# ASA.net
KiCad netlist of a schematic drawn in Altium Designer
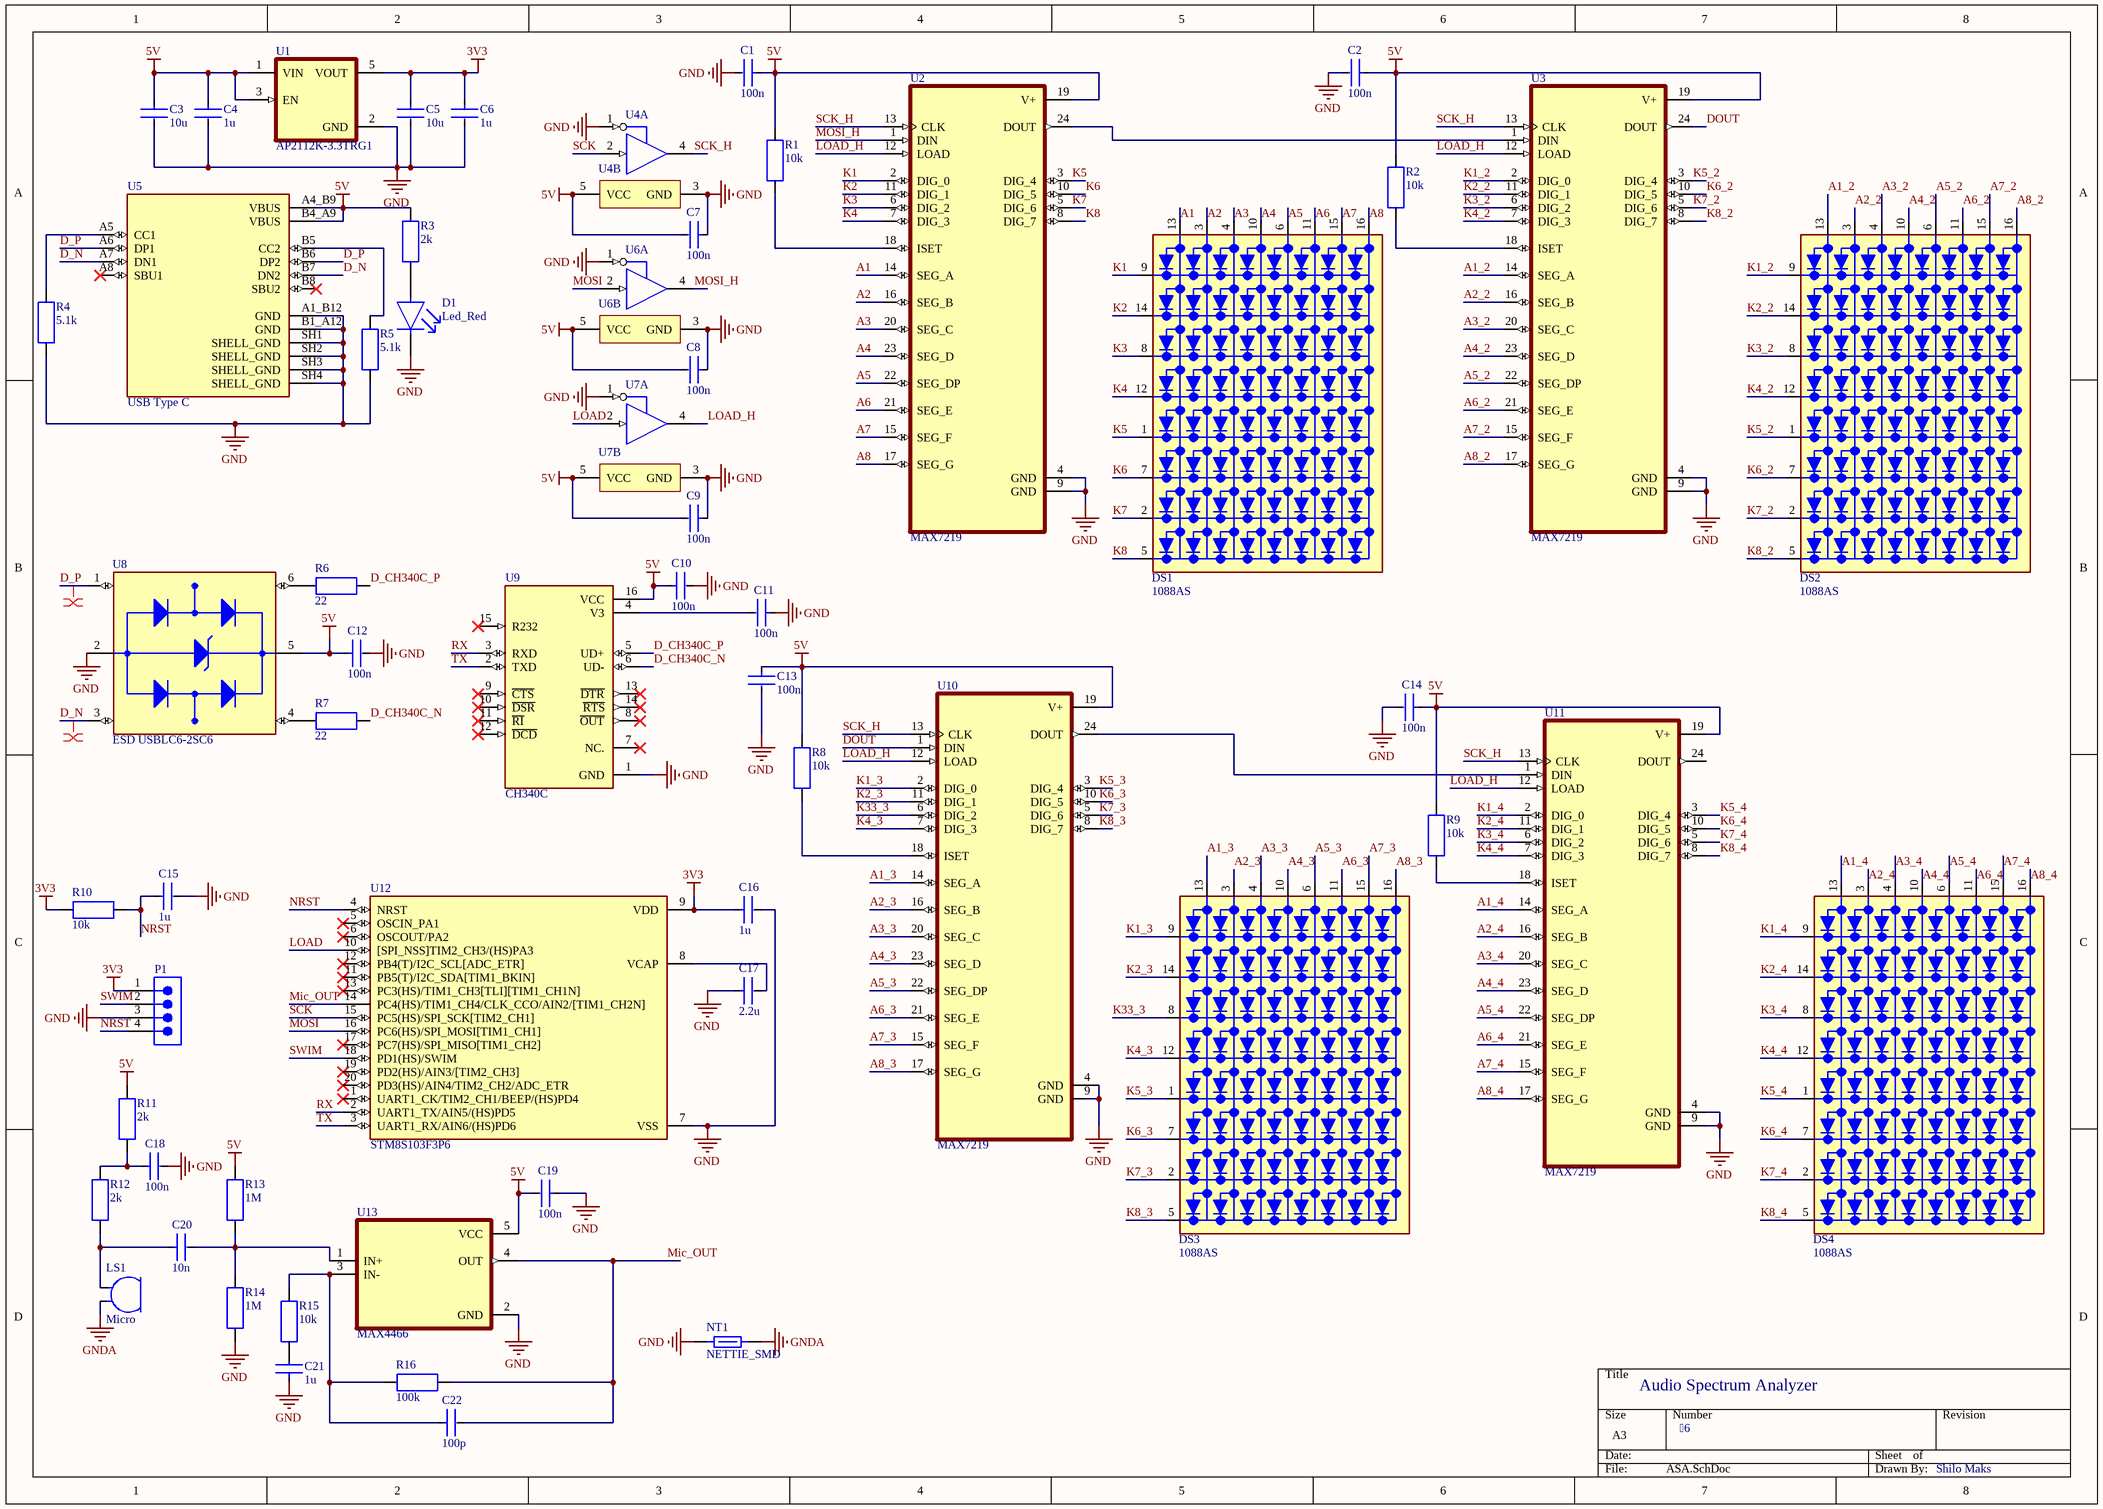
[diagram p0: ASA.SchDoc]

(export (version "E")
  (design (tool "Eeschema 10.0.6"))
  (components
    (comp (ref "C1")
      (value "100n")
      (footprint "Cap_1206")
      (fields (field (name "Comment") "Cap_1206"))
      (libsource (lib "Schlib_Spectrum_Analyzer") (part "Cap_1206"))
    )
    (comp (ref "C2")
      (value "100n")
      (footprint "Cap_1206")
      (fields (field (name "Comment") "Cap_1206"))
      (libsource (lib "Schlib_Spectrum_Analyzer") (part "Cap_1206"))
    )
    (comp (ref "C3")
      (value "10u")
      (footprint "Cap_1206")
      (fields (field (name "Comment") "Cap_1206"))
      (libsource (lib "Schlib_Spectrum_Analyzer") (part "Cap_1206"))
    )
    (comp (ref "C4")
      (value "1u")
      (footprint "Cap_1206")
      (fields (field (name "Comment") "Cap_1206"))
      (libsource (lib "Schlib_Spectrum_Analyzer") (part "Cap_1206"))
    )
    (comp (ref "C5")
      (value "10u")
      (footprint "Cap_1206")
      (fields (field (name "Comment") "Cap_1206"))
      (libsource (lib "Schlib_Spectrum_Analyzer") (part "Cap_1206"))
    )
    (comp (ref "C6")
      (value "1u")
      (footprint "Cap_1206")
      (fields (field (name "Comment") "Cap_1206"))
      (libsource (lib "Schlib_Spectrum_Analyzer") (part "Cap_1206"))
    )
    (comp (ref "C7")
      (value "100n")
      (footprint "Cap_1206")
      (fields (field (name "Comment") "Cap_1206"))
      (libsource (lib "Schlib_Spectrum_Analyzer") (part "Cap_1206"))
    )
    (comp (ref "C8")
      (value "100n")
      (footprint "Cap_1206")
      (fields (field (name "Comment") "Cap_1206"))
      (libsource (lib "Schlib_Spectrum_Analyzer") (part "Cap_1206"))
    )
    (comp (ref "C9")
      (value "100n")
      (footprint "Cap_1206")
      (fields (field (name "Comment") "Cap_1206"))
      (libsource (lib "Schlib_Spectrum_Analyzer") (part "Cap_1206"))
    )
    (comp (ref "C10")
      (value "100n")
      (footprint "Cap_1206")
      (fields (field (name "Comment") "Cap_1206"))
      (libsource (lib "Schlib_Spectrum_Analyzer") (part "Cap_1206"))
    )
    (comp (ref "C11")
      (value "100n")
      (footprint "Cap_1206")
      (fields (field (name "Comment") "Cap_1206"))
      (libsource (lib "Schlib_Spectrum_Analyzer") (part "Cap_1206"))
    )
    (comp (ref "C12")
      (value "100n")
      (footprint "Cap_1206")
      (fields (field (name "Comment") "Cap_1206"))
      (libsource (lib "Schlib_Spectrum_Analyzer") (part "Cap_1206"))
    )
    (comp (ref "C13")
      (value "100n")
      (footprint "Cap_1206")
      (fields (field (name "Comment") "Cap_1206"))
      (libsource (lib "Schlib_Spectrum_Analyzer") (part "Cap_1206"))
    )
    (comp (ref "C14")
      (value "100n")
      (footprint "Cap_1206")
      (fields (field (name "Comment") "Cap_1206"))
      (libsource (lib "Schlib_Spectrum_Analyzer") (part "Cap_1206"))
    )
    (comp (ref "C15")
      (value "1u")
      (footprint "Cap_1206")
      (fields (field (name "Comment") "Cap_1206"))
      (libsource (lib "Schlib_Spectrum_Analyzer") (part "Cap_1206"))
    )
    (comp (ref "C16")
      (value "1u")
      (footprint "Cap_1206")
      (libsource (lib "Schlib_Spectrum_Analyzer") (part "Cap_1206"))
    )
    (comp (ref "C17")
      (value "2.2u")
      (footprint "Cap_1206")
      (fields (field (name "Comment") "Cap_1206"))
      (libsource (lib "Schlib_Spectrum_Analyzer") (part "Cap_1206"))
    )
    (comp (ref "C18")
      (value "100n")
      (footprint "Cap_1206")
      (fields (field (name "Comment") "Cap_1206"))
      (libsource (lib "Schlib_Spectrum_Analyzer") (part "Cap_1206"))
    )
    (comp (ref "C19")
      (value "100n")
      (footprint "Cap_1206")
      (fields (field (name "Comment") "Cap_1206"))
      (libsource (lib "Schlib_Spectrum_Analyzer") (part "Cap_1206"))
    )
    (comp (ref "C20")
      (value "10n")
      (footprint "Cap_1206")
      (fields (field (name "Comment") "Cap_1206"))
      (libsource (lib "Schlib_Spectrum_Analyzer") (part "Cap_1206"))
    )
    (comp (ref "C21")
      (value "1u")
      (footprint "Cap_1206")
      (fields (field (name "Comment") "Cap_1206"))
      (libsource (lib "Schlib_Spectrum_Analyzer") (part "Cap_1206"))
    )
    (comp (ref "C22")
      (value "100p")
      (footprint "Cap_1206")
      (fields (field (name "Comment") "Cap_1206"))
      (libsource (lib "Schlib_Spectrum_Analyzer") (part "Cap_1206"))
    )
    (comp (ref "D1")
      (value "Led_Red")
      (footprint "Led_Red")
      (libsource (lib "Schlib_Spectrum_Analyzer") (part "Led_Red"))
    )
    (comp (ref "DS1")
      (value "1088AS")
      (footprint "LED_MATRIX_8x8_1088AS")
      (libsource (lib "Schlib_Spectrum_Analyzer") (part "1088AS"))
    )
    (comp (ref "DS2")
      (value "1088AS")
      (footprint "LED_MATRIX_8x8_1088AS")
      (libsource (lib "Schlib_Spectrum_Analyzer") (part "1088AS"))
    )
    (comp (ref "DS3")
      (value "1088AS")
      (footprint "LED_MATRIX_8x8_1088AS")
      (libsource (lib "Schlib_Spectrum_Analyzer") (part "1088AS"))
    )
    (comp (ref "DS4")
      (value "1088AS")
      (footprint "LED_MATRIX_8x8_1088AS")
      (libsource (lib "Schlib_Spectrum_Analyzer") (part "1088AS"))
    )
    (comp (ref "LS1")
      (value "Micro")
      (footprint "Micro")
      (libsource (lib "Schlib_Spectrum_Analyzer") (part "Micro"))
    )
    (comp (ref "NT1")
      (value "NETTIE_SMD")
      (footprint "NETTIE_SMD")
      (libsource (lib "Schlib_Spectrum_Analyzer") (part "NETTIE_SMD"))
    )
    (comp (ref "P1")
      (value "61300411021")
      (footprint "61300411021")
      (description "THT Angled Pin Header WR-PHD, Pitch 2.54 mm, Single Row, 4 pins")
      (libsource (lib "Altium Content Vault") (part "Header_Male_1R_04P"))
    )
    (comp (ref "R1")
      (value "10k")
      (footprint "Res_1206")
      (fields (field (name "Comment") "Res_1206"))
      (libsource (lib "Schlib_Spectrum_Analyzer") (part "Res_1206"))
    )
    (comp (ref "R2")
      (value "10k")
      (footprint "Res_1206")
      (fields (field (name "Comment") "Res_1206"))
      (libsource (lib "Schlib_Spectrum_Analyzer") (part "Res_1206"))
    )
    (comp (ref "R3")
      (value "2k")
      (footprint "Res_1206")
      (fields (field (name "Comment") "Res_1206"))
      (libsource (lib "Schlib_Spectrum_Analyzer") (part "Res_1206"))
    )
    (comp (ref "R4")
      (value "5.1k")
      (footprint "Res_1206")
      (fields (field (name "Comment") "Res_1206"))
      (libsource (lib "Schlib_Spectrum_Analyzer") (part "Res_1206"))
    )
    (comp (ref "R5")
      (value "5.1k")
      (footprint "Res_1206")
      (fields (field (name "Comment") "Res_1206"))
      (libsource (lib "Schlib_Spectrum_Analyzer") (part "Res_1206"))
    )
    (comp (ref "R6")
      (value "22")
      (footprint "Res_1206")
      (fields (field (name "Comment") "Res_1206"))
      (libsource (lib "Schlib_Spectrum_Analyzer") (part "Res_1206"))
    )
    (comp (ref "R7")
      (value "22")
      (footprint "Res_1206")
      (fields (field (name "Comment") "Res_1206"))
      (libsource (lib "Schlib_Spectrum_Analyzer") (part "Res_1206"))
    )
    (comp (ref "R8")
      (value "10k")
      (footprint "Res_1206")
      (fields (field (name "Comment") "Res_1206"))
      (libsource (lib "Schlib_Spectrum_Analyzer") (part "Res_1206"))
    )
    (comp (ref "R9")
      (value "10k")
      (footprint "Res_1206")
      (fields (field (name "Comment") "Res_1206"))
      (libsource (lib "Schlib_Spectrum_Analyzer") (part "Res_1206"))
    )
    (comp (ref "R10")
      (value "10k")
      (footprint "Res_1206")
      (fields (field (name "Comment") "Res_1206"))
      (libsource (lib "Schlib_Spectrum_Analyzer") (part "Res_1206"))
    )
    (comp (ref "R11")
      (value "2k")
      (footprint "Res_1206")
      (fields (field (name "Comment") "Res_1206"))
      (libsource (lib "Schlib_Spectrum_Analyzer") (part "Res_1206"))
    )
    (comp (ref "R12")
      (value "2k")
      (footprint "Res_1206")
      (fields (field (name "Comment") "Res_1206"))
      (libsource (lib "Schlib_Spectrum_Analyzer") (part "Res_1206"))
    )
    (comp (ref "R13")
      (value "1M")
      (footprint "Res_1206")
      (fields (field (name "Comment") "Res_1206"))
      (libsource (lib "Schlib_Spectrum_Analyzer") (part "Res_1206"))
    )
    (comp (ref "R14")
      (value "1M")
      (footprint "Res_1206")
      (fields (field (name "Comment") "Res_1206"))
      (libsource (lib "Schlib_Spectrum_Analyzer") (part "Res_1206"))
    )
    (comp (ref "R15")
      (value "10k")
      (footprint "Res_1206")
      (fields (field (name "Comment") "Res_1206"))
      (libsource (lib "Schlib_Spectrum_Analyzer") (part "Res_1206"))
    )
    (comp (ref "R16")
      (value "100k")
      (footprint "Res_1206")
      (fields (field (name "Comment") "Res_1206"))
      (libsource (lib "Schlib_Spectrum_Analyzer") (part "Res_1206"))
    )
    (comp (ref "U1")
      (value "AP2112K-3.3TRG1")
      (footprint "AP2112K-3.3TRG1")
      (libsource (lib "Schlib_Spectrum_Analyzer") (part "AP2112K-3.3TRG1"))
    )
    (comp (ref "U2")
      (value "MAX7219")
      (footprint "MAX7219")
      (libsource (lib "Schlib_Spectrum_Analyzer") (part "MAX7219"))
    )
    (comp (ref "U3")
      (value "MAX7219")
      (footprint "MAX7219")
      (libsource (lib "Schlib_Spectrum_Analyzer") (part "MAX7219"))
    )
    (comp (ref "U4")
      (value "CAHCT1G125QDCKRG4Q")
      (footprint "DCK0005A_M")
      (fields
        (field (name "GENERIC PART NUMBER") "SN74AHCT1G125-Q1")
        (field (name "MANUFACTURER") "Texas Instruments")
      )
      (libsource (lib "Schlib_Spectrum_Analyzer") (part "CMP-0859-00347-3"))
    )
    (comp (ref "U5")
      (value "USB Type C")
      (footprint "USB Type C")
      (libsource (lib "Schlib_Spectrum_Analyzer") (part "USB Type C"))
    )
    (comp (ref "U6")
      (value "CAHCT1G125QDCKRG4Q")
      (footprint "DCK0005A_M")
      (fields
        (field (name "GENERIC PART NUMBER") "SN74AHCT1G125-Q1")
        (field (name "MANUFACTURER") "Texas Instruments")
      )
      (libsource (lib "Schlib_Spectrum_Analyzer") (part "CMP-0859-00347-3"))
    )
    (comp (ref "U7")
      (value "CAHCT1G125QDCKRG4Q")
      (footprint "DCK0005A_M")
      (fields
        (field (name "GENERIC PART NUMBER") "SN74AHCT1G125-Q1")
        (field (name "MANUFACTURER") "Texas Instruments")
      )
      (libsource (lib "Schlib_Spectrum_Analyzer") (part "CMP-0859-00347-3"))
    )
    (comp (ref "U8")
      (value "ESD USBLC6-2SC6")
      (footprint "ESD USBLC6-2SC6")
      (libsource (lib "Schlib_Spectrum_Analyzer") (part "ESD USBLC6-2SC6"))
    )
    (comp (ref "U9")
      (value "CH340C")
      (footprint "CH340C")
      (libsource (lib "Schlib_Spectrum_Analyzer") (part "CH340C"))
    )
    (comp (ref "U10")
      (value "MAX7219")
      (footprint "MAX7219")
      (libsource (lib "Schlib_Spectrum_Analyzer") (part "MAX7219"))
    )
    (comp (ref "U11")
      (value "MAX7219")
      (footprint "MAX7219")
      (libsource (lib "Schlib_Spectrum_Analyzer") (part "MAX7219"))
    )
    (comp (ref "U12")
      (value "STM8S103F3P6")
      (footprint "STM8S103F3P6")
      (libsource (lib "Schlib_Spectrum_Analyzer") (part "STM8S103F3P6"))
    )
    (comp (ref "U13")
      (value "MAX4466")
      (footprint "MAX4466")
      (libsource (lib "Schlib_Spectrum_Analyzer") (part "MAX4466"))
    )
  )
  (nets
    (net (code "1") (name "/DOUT") (class "Default")
      (node (ref "U10") (pin "1") (pinfunction "DIN_1") (pintype "input"))
      (node (ref "U3") (pin "24") (pinfunction "DOUT_24") (pintype "output"))
    )
    (net (code "2") (name "/D_CH340C_N") (class "Default")
      (node (ref "R7") (pin "2") (pinfunction "2_2") (pintype "passive"))
      (node (ref "U9") (pin "6") (pinfunction "UD-_6") (pintype "bidirectional"))
    )
    (net (code "3") (name "/D_CH340C_P") (class "Default")
      (node (ref "R6") (pin "2") (pinfunction "2_2") (pintype "passive"))
      (node (ref "U9") (pin "5") (pinfunction "UD+_5") (pintype "bidirectional"))
    )
    (net (code "4") (name "/D_N") (class "Default")
      (node (ref "U5") (pin "A7") (pinfunction "DN1_A7") (pintype "bidirectional"))
      (node (ref "U5") (pin "B7") (pinfunction "DN2_B7") (pintype "bidirectional"))
      (node (ref "U8") (pin "3") (pinfunction "I/O2_IN_3") (pintype "bidirectional"))
    )
    (net (code "5") (name "/D_P") (class "Default")
      (node (ref "U5") (pin "A6") (pinfunction "DP1_A6") (pintype "bidirectional"))
      (node (ref "U5") (pin "B6") (pinfunction "DP2_B6") (pintype "bidirectional"))
      (node (ref "U8") (pin "1") (pinfunction "I/O1_IN_1") (pintype "bidirectional"))
    )
    (net (code "6") (name "/K1") (class "Default")
      (node (ref "DS1") (pin "9") (pinfunction "CATHODE_ROW_1_9") (pintype "passive"))
      (node (ref "U2") (pin "2") (pinfunction "DIG_0_2") (pintype "bidirectional"))
    )
    (net (code "7") (name "/K1_2") (class "Default")
      (node (ref "DS2") (pin "9") (pinfunction "CATHODE_ROW_1_9") (pintype "passive"))
      (node (ref "U3") (pin "2") (pinfunction "DIG_0_2") (pintype "bidirectional"))
    )
    (net (code "8") (name "/K1_3") (class "Default")
      (node (ref "DS3") (pin "9") (pinfunction "CATHODE_ROW_1_9") (pintype "passive"))
      (node (ref "U10") (pin "2") (pinfunction "DIG_0_2") (pintype "bidirectional"))
    )
    (net (code "9") (name "/K1_4") (class "Default")
      (node (ref "DS4") (pin "9") (pinfunction "CATHODE_ROW_1_9") (pintype "passive"))
      (node (ref "U11") (pin "2") (pinfunction "DIG_0_2") (pintype "bidirectional"))
    )
    (net (code "10") (name "/K2") (class "Default")
      (node (ref "DS1") (pin "14") (pinfunction "CATHODE_ROW_2_14") (pintype "passive"))
      (node (ref "U2") (pin "11") (pinfunction "DIG_1_11") (pintype "bidirectional"))
    )
    (net (code "11") (name "/K2_2") (class "Default")
      (node (ref "DS2") (pin "14") (pinfunction "CATHODE_ROW_2_14") (pintype "passive"))
      (node (ref "U3") (pin "11") (pinfunction "DIG_1_11") (pintype "bidirectional"))
    )
    (net (code "12") (name "/K2_3") (class "Default")
      (node (ref "DS3") (pin "14") (pinfunction "CATHODE_ROW_2_14") (pintype "passive"))
      (node (ref "U10") (pin "11") (pinfunction "DIG_1_11") (pintype "bidirectional"))
    )
    (net (code "13") (name "/K2_4") (class "Default")
      (node (ref "DS4") (pin "14") (pinfunction "CATHODE_ROW_2_14") (pintype "passive"))
      (node (ref "U11") (pin "11") (pinfunction "DIG_1_11") (pintype "bidirectional"))
    )
    (net (code "14") (name "/K3") (class "Default")
      (node (ref "DS1") (pin "8") (pinfunction "CATHODE_ROW_3_8") (pintype "passive"))
      (node (ref "U2") (pin "6") (pinfunction "DIG_2_6") (pintype "bidirectional"))
    )
    (net (code "15") (name "/K3_2") (class "Default")
      (node (ref "DS2") (pin "8") (pinfunction "CATHODE_ROW_3_8") (pintype "passive"))
      (node (ref "U3") (pin "6") (pinfunction "DIG_2_6") (pintype "bidirectional"))
    )
    (net (code "16") (name "/K3_4") (class "Default")
      (node (ref "DS4") (pin "8") (pinfunction "CATHODE_ROW_3_8") (pintype "passive"))
      (node (ref "U11") (pin "6") (pinfunction "DIG_2_6") (pintype "bidirectional"))
    )
    (net (code "17") (name "/K4") (class "Default")
      (node (ref "DS1") (pin "12") (pinfunction "CATHODE_ROW_4_12") (pintype "passive"))
      (node (ref "U2") (pin "7") (pinfunction "DIG_3_7") (pintype "bidirectional"))
    )
    (net (code "18") (name "/K4_2") (class "Default")
      (node (ref "DS2") (pin "12") (pinfunction "CATHODE_ROW_4_12") (pintype "passive"))
      (node (ref "U3") (pin "7") (pinfunction "DIG_3_7") (pintype "bidirectional"))
    )
    (net (code "19") (name "/K4_3") (class "Default")
      (node (ref "DS3") (pin "12") (pinfunction "CATHODE_ROW_4_12") (pintype "passive"))
      (node (ref "U10") (pin "7") (pinfunction "DIG_3_7") (pintype "bidirectional"))
    )
    (net (code "20") (name "/K4_4") (class "Default")
      (node (ref "DS4") (pin "12") (pinfunction "CATHODE_ROW_4_12") (pintype "passive"))
      (node (ref "U11") (pin "7") (pinfunction "DIG_3_7") (pintype "bidirectional"))
    )
    (net (code "21") (name "/K5") (class "Default")
      (node (ref "DS1") (pin "1") (pinfunction "CATHODE_ROW_5_1") (pintype "passive"))
      (node (ref "U2") (pin "3") (pinfunction "DIG_4_3") (pintype "bidirectional"))
    )
    (net (code "22") (name "/K5_2") (class "Default")
      (node (ref "DS2") (pin "1") (pinfunction "CATHODE_ROW_5_1") (pintype "passive"))
      (node (ref "U3") (pin "3") (pinfunction "DIG_4_3") (pintype "bidirectional"))
    )
    (net (code "23") (name "/K5_3") (class "Default")
      (node (ref "DS3") (pin "1") (pinfunction "CATHODE_ROW_5_1") (pintype "passive"))
      (node (ref "U10") (pin "3") (pinfunction "DIG_4_3") (pintype "bidirectional"))
    )
    (net (code "24") (name "/K5_4") (class "Default")
      (node (ref "DS4") (pin "1") (pinfunction "CATHODE_ROW_5_1") (pintype "passive"))
      (node (ref "U11") (pin "3") (pinfunction "DIG_4_3") (pintype "bidirectional"))
    )
    (net (code "25") (name "/K6") (class "Default")
      (node (ref "DS1") (pin "7") (pinfunction "CATHODE_ROW_6_7") (pintype "passive"))
      (node (ref "U2") (pin "10") (pinfunction "DIG_5_10") (pintype "bidirectional"))
    )
    (net (code "26") (name "/K6_2") (class "Default")
      (node (ref "DS2") (pin "7") (pinfunction "CATHODE_ROW_6_7") (pintype "passive"))
      (node (ref "U3") (pin "10") (pinfunction "DIG_5_10") (pintype "bidirectional"))
    )
    (net (code "27") (name "/K6_3") (class "Default")
      (node (ref "DS3") (pin "7") (pinfunction "CATHODE_ROW_6_7") (pintype "passive"))
      (node (ref "U10") (pin "10") (pinfunction "DIG_5_10") (pintype "bidirectional"))
    )
    (net (code "28") (name "/K6_4") (class "Default")
      (node (ref "DS4") (pin "7") (pinfunction "CATHODE_ROW_6_7") (pintype "passive"))
      (node (ref "U11") (pin "10") (pinfunction "DIG_5_10") (pintype "bidirectional"))
    )
    (net (code "29") (name "/K7") (class "Default")
      (node (ref "DS1") (pin "2") (pinfunction "CATHODE_ROW_7_2") (pintype "passive"))
      (node (ref "U2") (pin "5") (pinfunction "DIG_6_5") (pintype "bidirectional"))
    )
    (net (code "30") (name "/K7_2") (class "Default")
      (node (ref "DS2") (pin "2") (pinfunction "CATHODE_ROW_7_2") (pintype "passive"))
      (node (ref "U3") (pin "5") (pinfunction "DIG_6_5") (pintype "bidirectional"))
    )
    (net (code "31") (name "/K7_3") (class "Default")
      (node (ref "DS3") (pin "2") (pinfunction "CATHODE_ROW_7_2") (pintype "passive"))
      (node (ref "U10") (pin "5") (pinfunction "DIG_6_5") (pintype "bidirectional"))
    )
    (net (code "32") (name "/K7_4") (class "Default")
      (node (ref "DS4") (pin "2") (pinfunction "CATHODE_ROW_7_2") (pintype "passive"))
      (node (ref "U11") (pin "5") (pinfunction "DIG_6_5") (pintype "bidirectional"))
    )
    (net (code "33") (name "/K8") (class "Default")
      (node (ref "DS1") (pin "5") (pinfunction "CATHODE_ROW_8_5") (pintype "passive"))
      (node (ref "U2") (pin "8") (pinfunction "DIG_7_8") (pintype "bidirectional"))
    )
    (net (code "34") (name "/K8_2") (class "Default")
      (node (ref "DS2") (pin "5") (pinfunction "CATHODE_ROW_8_5") (pintype "passive"))
      (node (ref "U3") (pin "8") (pinfunction "DIG_7_8") (pintype "bidirectional"))
    )
    (net (code "35") (name "/K8_3") (class "Default")
      (node (ref "DS3") (pin "5") (pinfunction "CATHODE_ROW_8_5") (pintype "passive"))
      (node (ref "U10") (pin "8") (pinfunction "DIG_7_8") (pintype "bidirectional"))
    )
    (net (code "36") (name "/K8_4") (class "Default")
      (node (ref "DS4") (pin "5") (pinfunction "CATHODE_ROW_8_5") (pintype "passive"))
      (node (ref "U11") (pin "8") (pinfunction "DIG_7_8") (pintype "bidirectional"))
    )
    (net (code "37") (name "/K33_3") (class "Default")
      (node (ref "DS3") (pin "8") (pinfunction "CATHODE_ROW_3_8") (pintype "passive"))
      (node (ref "U10") (pin "6") (pinfunction "DIG_2_6") (pintype "bidirectional"))
    )
    (net (code "38") (name "/LOAD") (class "Default")
      (node (ref "U12") (pin "10") (pinfunction "[SPI_NSS]TIM2_CH3/(HS)PA3_10") (pintype "bidirectional"))
      (node (ref "U7") (pin "2") (pinfunction "A_2") (pintype "input"))
    )
    (net (code "39") (name "/LOAD_H") (class "Default")
      (node (ref "U10") (pin "12") (pinfunction "LOAD_12") (pintype "input"))
      (node (ref "U11") (pin "12") (pinfunction "LOAD_12") (pintype "input"))
      (node (ref "U2") (pin "12") (pinfunction "LOAD_12") (pintype "input"))
      (node (ref "U3") (pin "12") (pinfunction "LOAD_12") (pintype "input"))
      (node (ref "U7") (pin "4") (pinfunction "Y_4") (pintype "tri_state"))
    )
    (net (code "40") (name "/MOSI") (class "Default")
      (node (ref "U12") (pin "16") (pinfunction "PC6(HS)/SPI_MOSI[TIM1_CH1]_16") (pintype "bidirectional"))
      (node (ref "U6") (pin "2") (pinfunction "A_2") (pintype "input"))
    )
    (net (code "41") (name "/MOSI_H") (class "Default")
      (node (ref "U2") (pin "1") (pinfunction "DIN_1") (pintype "input"))
      (node (ref "U6") (pin "4") (pinfunction "Y_4") (pintype "tri_state"))
    )
    (net (code "42") (name "/Mic_OUT") (class "Default")
      (node (ref "C22") (pin "1") (pinfunction "1_1") (pintype "passive"))
      (node (ref "R16") (pin "2") (pinfunction "2_2") (pintype "passive"))
      (node (ref "U12") (pin "14") (pinfunction "PC4(HS)/TIM1_CH4/CLK_CCO/AIN2/[TIM1_CH2N]_14") (pintype "passive"))
      (node (ref "U13") (pin "4") (pinfunction "OUT_4") (pintype "output"))
    )
    (net (code "43") (name "/NRST") (class "Default")
      (node (ref "C15") (pin "2") (pinfunction "2_2") (pintype "passive"))
      (node (ref "P1") (pin "4") (pinfunction "4_4") (pintype "passive"))
      (node (ref "R10") (pin "1") (pinfunction "1_1") (pintype "passive"))
      (node (ref "U12") (pin "4") (pinfunction "NRST_4") (pintype "bidirectional"))
    )
    (net (code "44") (name "/RX") (class "Default")
      (node (ref "U12") (pin "2") (pinfunction "UART1_TX/AIN5/(HS)PD5_2") (pintype "bidirectional"))
      (node (ref "U9") (pin "3") (pinfunction "RXD_3") (pintype "bidirectional"))
    )
    (net (code "45") (name "/SCK") (class "Default")
      (node (ref "U12") (pin "15") (pinfunction "PC5(HS)/SPI_SCK[TIM2_CH1]_15") (pintype "bidirectional"))
      (node (ref "U4") (pin "2") (pinfunction "A_2") (pintype "input"))
    )
    (net (code "46") (name "/SCK_H") (class "Default")
      (node (ref "U10") (pin "13") (pinfunction "CLK_13") (pintype "input"))
      (node (ref "U11") (pin "13") (pinfunction "CLK_13") (pintype "input"))
      (node (ref "U2") (pin "13") (pinfunction "CLK_13") (pintype "input"))
      (node (ref "U3") (pin "13") (pinfunction "CLK_13") (pintype "input"))
      (node (ref "U4") (pin "4") (pinfunction "Y_4") (pintype "tri_state"))
    )
    (net (code "47") (name "/SWIM") (class "Default")
      (node (ref "P1") (pin "2") (pinfunction "2_2") (pintype "passive"))
      (node (ref "U12") (pin "18") (pinfunction "PD1(HS)/SWIM_18") (pintype "bidirectional"))
    )
    (net (code "48") (name "/TX") (class "Default")
      (node (ref "U12") (pin "3") (pinfunction "UART1_RX/AIN6/(HS)PD6_3") (pintype "bidirectional"))
      (node (ref "U9") (pin "2") (pinfunction "TXD_2") (pintype "bidirectional"))
    )
    (net (code "49") (name "/А1") (class "Default")
      (node (ref "DS1") (pin "13") (pinfunction "ANODE_COLUMN_1_13") (pintype "passive"))
      (node (ref "U2") (pin "14") (pinfunction "SEG_A_14") (pintype "bidirectional"))
    )
    (net (code "50") (name "/А1_2") (class "Default")
      (node (ref "DS2") (pin "13") (pinfunction "ANODE_COLUMN_1_13") (pintype "passive"))
      (node (ref "U3") (pin "14") (pinfunction "SEG_A_14") (pintype "bidirectional"))
    )
    (net (code "51") (name "/А1_3") (class "Default")
      (node (ref "DS3") (pin "13") (pinfunction "ANODE_COLUMN_1_13") (pintype "passive"))
      (node (ref "U10") (pin "14") (pinfunction "SEG_A_14") (pintype "bidirectional"))
    )
    (net (code "52") (name "/А1_4") (class "Default")
      (node (ref "DS4") (pin "13") (pinfunction "ANODE_COLUMN_1_13") (pintype "passive"))
      (node (ref "U11") (pin "14") (pinfunction "SEG_A_14") (pintype "bidirectional"))
    )
    (net (code "53") (name "/А2") (class "Default")
      (node (ref "DS1") (pin "3") (pinfunction "ANODE_COLUMN_2_3") (pintype "passive"))
      (node (ref "U2") (pin "16") (pinfunction "SEG_B_16") (pintype "bidirectional"))
    )
    (net (code "54") (name "/А2_2") (class "Default")
      (node (ref "DS2") (pin "3") (pinfunction "ANODE_COLUMN_2_3") (pintype "passive"))
      (node (ref "U3") (pin "16") (pinfunction "SEG_B_16") (pintype "bidirectional"))
    )
    (net (code "55") (name "/А2_3") (class "Default")
      (node (ref "DS3") (pin "3") (pinfunction "ANODE_COLUMN_2_3") (pintype "passive"))
      (node (ref "U10") (pin "16") (pinfunction "SEG_B_16") (pintype "bidirectional"))
    )
    (net (code "56") (name "/А2_4") (class "Default")
      (node (ref "DS4") (pin "3") (pinfunction "ANODE_COLUMN_2_3") (pintype "passive"))
      (node (ref "U11") (pin "16") (pinfunction "SEG_B_16") (pintype "bidirectional"))
    )
    (net (code "57") (name "/А3") (class "Default")
      (node (ref "DS1") (pin "4") (pinfunction "ANODE_COLUMN_3_4") (pintype "passive"))
      (node (ref "U2") (pin "20") (pinfunction "SEG_C_20") (pintype "bidirectional"))
    )
    (net (code "58") (name "/А3_2") (class "Default")
      (node (ref "DS2") (pin "4") (pinfunction "ANODE_COLUMN_3_4") (pintype "passive"))
      (node (ref "U3") (pin "20") (pinfunction "SEG_C_20") (pintype "bidirectional"))
    )
    (net (code "59") (name "/А3_3") (class "Default")
      (node (ref "DS3") (pin "4") (pinfunction "ANODE_COLUMN_3_4") (pintype "passive"))
      (node (ref "U10") (pin "20") (pinfunction "SEG_C_20") (pintype "bidirectional"))
    )
    (net (code "60") (name "/А3_4") (class "Default")
      (node (ref "DS4") (pin "4") (pinfunction "ANODE_COLUMN_3_4") (pintype "passive"))
      (node (ref "U11") (pin "20") (pinfunction "SEG_C_20") (pintype "bidirectional"))
    )
    (net (code "61") (name "/А4") (class "Default")
      (node (ref "DS1") (pin "10") (pinfunction "ANODE_COLUMN_4_10") (pintype "passive"))
      (node (ref "U2") (pin "23") (pinfunction "SEG_D_23") (pintype "bidirectional"))
    )
    (net (code "62") (name "/А4_2") (class "Default")
      (node (ref "DS2") (pin "10") (pinfunction "ANODE_COLUMN_4_10") (pintype "passive"))
      (node (ref "U3") (pin "23") (pinfunction "SEG_D_23") (pintype "bidirectional"))
    )
    (net (code "63") (name "/А4_3") (class "Default")
      (node (ref "DS3") (pin "10") (pinfunction "ANODE_COLUMN_4_10") (pintype "passive"))
      (node (ref "U10") (pin "23") (pinfunction "SEG_D_23") (pintype "bidirectional"))
    )
    (net (code "64") (name "/А4_4") (class "Default")
      (node (ref "DS4") (pin "10") (pinfunction "ANODE_COLUMN_4_10") (pintype "passive"))
      (node (ref "U11") (pin "23") (pinfunction "SEG_D_23") (pintype "bidirectional"))
    )
    (net (code "65") (name "/А5") (class "Default")
      (node (ref "DS1") (pin "6") (pinfunction "ANODE_COLUMN_5_6") (pintype "passive"))
      (node (ref "U2") (pin "22") (pinfunction "SEG_DP_22") (pintype "bidirectional"))
    )
    (net (code "66") (name "/А5_2") (class "Default")
      (node (ref "DS2") (pin "6") (pinfunction "ANODE_COLUMN_5_6") (pintype "passive"))
      (node (ref "U3") (pin "22") (pinfunction "SEG_DP_22") (pintype "bidirectional"))
    )
    (net (code "67") (name "/А5_3") (class "Default")
      (node (ref "DS3") (pin "6") (pinfunction "ANODE_COLUMN_5_6") (pintype "passive"))
      (node (ref "U10") (pin "22") (pinfunction "SEG_DP_22") (pintype "bidirectional"))
    )
    (net (code "68") (name "/А5_4") (class "Default")
      (node (ref "DS4") (pin "6") (pinfunction "ANODE_COLUMN_5_6") (pintype "passive"))
      (node (ref "U11") (pin "22") (pinfunction "SEG_DP_22") (pintype "bidirectional"))
    )
    (net (code "69") (name "/А6") (class "Default")
      (node (ref "DS1") (pin "11") (pinfunction "ANODE_COLUMN_6_11") (pintype "passive"))
      (node (ref "U2") (pin "21") (pinfunction "SEG_E_21") (pintype "bidirectional"))
    )
    (net (code "70") (name "/А6_2") (class "Default")
      (node (ref "DS2") (pin "11") (pinfunction "ANODE_COLUMN_6_11") (pintype "passive"))
      (node (ref "U3") (pin "21") (pinfunction "SEG_E_21") (pintype "bidirectional"))
    )
    (net (code "71") (name "/А6_3") (class "Default")
      (node (ref "DS3") (pin "11") (pinfunction "ANODE_COLUMN_6_11") (pintype "passive"))
      (node (ref "U10") (pin "21") (pinfunction "SEG_E_21") (pintype "bidirectional"))
    )
    (net (code "72") (name "/А6_4") (class "Default")
      (node (ref "DS4") (pin "11") (pinfunction "ANODE_COLUMN_6_11") (pintype "passive"))
      (node (ref "U11") (pin "21") (pinfunction "SEG_E_21") (pintype "bidirectional"))
    )
    (net (code "73") (name "/А7") (class "Default")
      (node (ref "DS1") (pin "15") (pinfunction "ANODE_COLUMN_7_15") (pintype "passive"))
      (node (ref "U2") (pin "15") (pinfunction "SEG_F_15") (pintype "bidirectional"))
    )
    (net (code "74") (name "/А7_2") (class "Default")
      (node (ref "DS2") (pin "15") (pinfunction "ANODE_COLUMN_7_15") (pintype "passive"))
      (node (ref "U3") (pin "15") (pinfunction "SEG_F_15") (pintype "bidirectional"))
    )
    (net (code "75") (name "/А7_3") (class "Default")
      (node (ref "DS3") (pin "15") (pinfunction "ANODE_COLUMN_7_15") (pintype "passive"))
      (node (ref "U10") (pin "15") (pinfunction "SEG_F_15") (pintype "bidirectional"))
    )
    (net (code "76") (name "/А7_4") (class "Default")
      (node (ref "DS4") (pin "15") (pinfunction "ANODE_COLUMN_7_15") (pintype "passive"))
      (node (ref "U11") (pin "15") (pinfunction "SEG_F_15") (pintype "bidirectional"))
    )
    (net (code "77") (name "/А8") (class "Default")
      (node (ref "DS1") (pin "16") (pinfunction "ANODE_COLUMN_8_16") (pintype "passive"))
      (node (ref "U2") (pin "17") (pinfunction "SEG_G_17") (pintype "bidirectional"))
    )
    (net (code "78") (name "/А8_2") (class "Default")
      (node (ref "DS2") (pin "16") (pinfunction "ANODE_COLUMN_8_16") (pintype "passive"))
      (node (ref "U3") (pin "17") (pinfunction "SEG_G_17") (pintype "bidirectional"))
    )
    (net (code "79") (name "/А8_3") (class "Default")
      (node (ref "DS3") (pin "16") (pinfunction "ANODE_COLUMN_8_16") (pintype "passive"))
      (node (ref "U10") (pin "17") (pinfunction "SEG_G_17") (pintype "bidirectional"))
    )
    (net (code "80") (name "/А8_4") (class "Default")
      (node (ref "DS4") (pin "16") (pinfunction "ANODE_COLUMN_8_16") (pintype "passive"))
      (node (ref "U11") (pin "17") (pinfunction "SEG_G_17") (pintype "bidirectional"))
    )
    (net (code "81") (name "3V3") (class "Default")
      (node (ref "C16") (pin "2") (pinfunction "2_2") (pintype "passive"))
      (node (ref "C5") (pin "2") (pinfunction "2_2") (pintype "passive"))
      (node (ref "C6") (pin "2") (pinfunction "2_2") (pintype "passive"))
      (node (ref "P1") (pin "1") (pinfunction "1_1") (pintype "passive"))
      (node (ref "R10") (pin "2") (pinfunction "2_2") (pintype "passive"))
      (node (ref "U1") (pin "5") (pinfunction "VOUT_5") (pintype "power_in"))
      (node (ref "U12") (pin "9") (pinfunction "VDD_9") (pintype "power_in"))
    )
    (net (code "82") (name "5V") (class "Default")
      (node (ref "C1") (pin "2") (pinfunction "2_2") (pintype "passive"))
      (node (ref "C10") (pin "2") (pinfunction "2_2") (pintype "passive"))
      (node (ref "C12") (pin "2") (pinfunction "2_2") (pintype "passive"))
      (node (ref "C13") (pin "2") (pinfunction "2_2") (pintype "passive"))
      (node (ref "C14") (pin "2") (pinfunction "2_2") (pintype "passive"))
      (node (ref "C19") (pin "1") (pinfunction "1_1") (pintype "passive"))
      (node (ref "C2") (pin "2") (pinfunction "2_2") (pintype "passive"))
      (node (ref "C3") (pin "2") (pinfunction "2_2") (pintype "passive"))
      (node (ref "C4") (pin "2") (pinfunction "2_2") (pintype "passive"))
      (node (ref "C7") (pin "1") (pinfunction "1_1") (pintype "passive"))
      (node (ref "C8") (pin "1") (pinfunction "1_1") (pintype "passive"))
      (node (ref "C9") (pin "1") (pinfunction "1_1") (pintype "passive"))
      (node (ref "R1") (pin "1") (pinfunction "1_1") (pintype "passive"))
      (node (ref "R11") (pin "1") (pinfunction "1_1") (pintype "passive"))
      (node (ref "R13") (pin "1") (pinfunction "1_1") (pintype "passive"))
      (node (ref "R2") (pin "1") (pinfunction "1_1") (pintype "passive"))
      (node (ref "R3") (pin "1") (pinfunction "1_1") (pintype "passive"))
      (node (ref "R8") (pin "1") (pinfunction "1_1") (pintype "passive"))
      (node (ref "R9") (pin "1") (pinfunction "1_1") (pintype "passive"))
      (node (ref "U1") (pin "1") (pinfunction "VIN_1") (pintype "power_in"))
      (node (ref "U1") (pin "3") (pinfunction "EN_3") (pintype "input"))
      (node (ref "U10") (pin "19") (pinfunction "V+_19") (pintype "power_in"))
      (node (ref "U11") (pin "19") (pinfunction "V+_19") (pintype "power_in"))
      (node (ref "U13") (pin "5") (pinfunction "VCC_5") (pintype "power_in"))
      (node (ref "U2") (pin "19") (pinfunction "V+_19") (pintype "power_in"))
      (node (ref "U3") (pin "19") (pinfunction "V+_19") (pintype "power_in"))
      (node (ref "U4") (pin "5") (pinfunction "VCC_5") (pintype "power_in"))
      (node (ref "U5") (pin "A4_B9") (pinfunction "VBUS_A4_B9") (pintype "power_in"))
      (node (ref "U5") (pin "B4_A9") (pinfunction "VBUS_B4_A9") (pintype "power_in"))
      (node (ref "U6") (pin "5") (pinfunction "VCC_5") (pintype "power_in"))
      (node (ref "U7") (pin "5") (pinfunction "VCC_5") (pintype "power_in"))
      (node (ref "U8") (pin "5") (pinfunction "VBUS_5") (pintype "power_in"))
      (node (ref "U9") (pin "16") (pinfunction "VCC_16") (pintype "power_in"))
    )
    (net (code "83") (name "GND") (class "Default")
      (node (ref "C1") (pin "1") (pinfunction "1_1") (pintype "passive"))
      (node (ref "C10") (pin "1") (pinfunction "1_1") (pintype "passive"))
      (node (ref "C11") (pin "2") (pinfunction "2_2") (pintype "passive"))
      (node (ref "C12") (pin "1") (pinfunction "1_1") (pintype "passive"))
      (node (ref "C13") (pin "1") (pinfunction "1_1") (pintype "passive"))
      (node (ref "C14") (pin "1") (pinfunction "1_1") (pintype "passive"))
      (node (ref "C15") (pin "1") (pinfunction "1_1") (pintype "passive"))
      (node (ref "C16") (pin "1") (pinfunction "1_1") (pintype "passive"))
      (node (ref "C17") (pin "2") (pinfunction "2_2") (pintype "passive"))
      (node (ref "C18") (pin "1") (pinfunction "1_1") (pintype "passive"))
      (node (ref "C19") (pin "2") (pinfunction "2_2") (pintype "passive"))
      (node (ref "C2") (pin "1") (pinfunction "1_1") (pintype "passive"))
      (node (ref "C21") (pin "2") (pinfunction "2_2") (pintype "passive"))
      (node (ref "C3") (pin "1") (pinfunction "1_1") (pintype "passive"))
      (node (ref "C4") (pin "1") (pinfunction "1_1") (pintype "passive"))
      (node (ref "C5") (pin "1") (pinfunction "1_1") (pintype "passive"))
      (node (ref "C6") (pin "1") (pinfunction "1_1") (pintype "passive"))
      (node (ref "C7") (pin "2") (pinfunction "2_2") (pintype "passive"))
      (node (ref "C8") (pin "2") (pinfunction "2_2") (pintype "passive"))
      (node (ref "C9") (pin "2") (pinfunction "2_2") (pintype "passive"))
      (node (ref "D1") (pin "1") (pinfunction "C_1") (pintype "passive"))
      (node (ref "NT1") (pin "1") (pinfunction "1_1") (pintype "passive"))
      (node (ref "P1") (pin "3") (pinfunction "3_3") (pintype "passive"))
      (node (ref "R14") (pin "2") (pinfunction "2_2") (pintype "passive"))
      (node (ref "R4") (pin "1") (pinfunction "1_1") (pintype "passive"))
      (node (ref "R5") (pin "1") (pinfunction "1_1") (pintype "passive"))
      (node (ref "U1") (pin "2") (pinfunction "GND_2") (pintype "power_in"))
      (node (ref "U10") (pin "4") (pinfunction "GND_4") (pintype "power_in"))
      (node (ref "U10") (pin "9") (pinfunction "GND_9") (pintype "power_in"))
      (node (ref "U11") (pin "4") (pinfunction "GND_4") (pintype "power_in"))
      (node (ref "U11") (pin "9") (pinfunction "GND_9") (pintype "power_in"))
      (node (ref "U12") (pin "7") (pinfunction "VSS_7") (pintype "power_in"))
      (node (ref "U13") (pin "2") (pinfunction "GND_2") (pintype "power_in"))
      (node (ref "U2") (pin "4") (pinfunction "GND_4") (pintype "power_in"))
      (node (ref "U2") (pin "9") (pinfunction "GND_9") (pintype "power_in"))
      (node (ref "U3") (pin "4") (pinfunction "GND_4") (pintype "power_in"))
      (node (ref "U3") (pin "9") (pinfunction "GND_9") (pintype "power_in"))
      (node (ref "U4") (pin "1") (pinfunction "~{OE}_1") (pintype "input"))
      (node (ref "U4") (pin "3") (pinfunction "GND_3") (pintype "power_in"))
      (node (ref "U5") (pin "A1_B12") (pinfunction "GND_A1_B12") (pintype "power_in"))
      (node (ref "U5") (pin "B1_A12") (pinfunction "GND_B1_A12") (pintype "power_in"))
      (node (ref "U5") (pin "SH1") (pinfunction "SHELL_GND_SH1") (pintype "power_in"))
      (node (ref "U5") (pin "SH2") (pinfunction "SHELL_GND_SH2") (pintype "power_in"))
      (node (ref "U5") (pin "SH3") (pinfunction "SHELL_GND_SH3") (pintype "power_in"))
      (node (ref "U5") (pin "SH4") (pinfunction "SHELL_GND_SH4") (pintype "power_in"))
      (node (ref "U6") (pin "1") (pinfunction "~{OE}_1") (pintype "input"))
      (node (ref "U6") (pin "3") (pinfunction "GND_3") (pintype "power_in"))
      (node (ref "U7") (pin "1") (pinfunction "~{OE}_1") (pintype "input"))
      (node (ref "U7") (pin "3") (pinfunction "GND_3") (pintype "power_in"))
      (node (ref "U8") (pin "2") (pinfunction "GND_2") (pintype "power_in"))
      (node (ref "U9") (pin "1") (pinfunction "GND_1") (pintype "power_in"))
    )
    (net (code "84") (name "GNDA") (class "Default")
      (node (ref "LS1") (pin "2") (pinfunction "C_2") (pintype "passive"))
      (node (ref "NT1") (pin "2") (pinfunction "2_2") (pintype "passive"))
    )
    (net (code "85") (name "Net-(C18-Pad2)") (class "Default")
      (node (ref "C18") (pin "2") (pinfunction "2_2") (pintype "passive"))
      (node (ref "R11") (pin "2") (pinfunction "2_2") (pintype "passive"))
      (node (ref "R12") (pin "1") (pinfunction "1_1") (pintype "passive"))
    )
    (net (code "86") (name "Net-(C21-Pad1)") (class "Default")
      (node (ref "C21") (pin "1") (pinfunction "1_1") (pintype "passive"))
      (node (ref "R15") (pin "2") (pinfunction "2_2") (pintype "passive"))
    )
    (net (code "87") (name "Net-(D1-A)") (class "Default")
      (node (ref "D1") (pin "2") (pinfunction "A_2") (pintype "passive"))
      (node (ref "R3") (pin "2") (pinfunction "2_2") (pintype "passive"))
    )
    (net (code "88") (name "Net-(LS1-A)") (class "Default")
      (node (ref "C20") (pin "2") (pinfunction "2_2") (pintype "passive"))
      (node (ref "LS1") (pin "1") (pinfunction "A_1") (pintype "passive"))
      (node (ref "R12") (pin "2") (pinfunction "2_2") (pintype "passive"))
    )
    (net (code "89") (name "Net-(U2-DOUT)") (class "Default")
      (node (ref "U2") (pin "24") (pinfunction "DOUT_24") (pintype "output"))
      (node (ref "U3") (pin "1") (pinfunction "DIN_1") (pintype "input"))
    )
    (net (code "90") (name "Net-(U2-ISET)") (class "Default")
      (node (ref "R1") (pin "2") (pinfunction "2_2") (pintype "passive"))
      (node (ref "U2") (pin "18") (pinfunction "ISET_18") (pintype "bidirectional"))
    )
    (net (code "91") (name "Net-(U3-ISET)") (class "Default")
      (node (ref "R2") (pin "2") (pinfunction "2_2") (pintype "passive"))
      (node (ref "U3") (pin "18") (pinfunction "ISET_18") (pintype "bidirectional"))
    )
    (net (code "92") (name "Net-(U5-CC1)") (class "Default")
      (node (ref "R4") (pin "2") (pinfunction "2_2") (pintype "passive"))
      (node (ref "U5") (pin "A5") (pinfunction "CC1_A5") (pintype "bidirectional"))
    )
    (net (code "93") (name "Net-(U5-CC2)") (class "Default")
      (node (ref "R5") (pin "2") (pinfunction "2_2") (pintype "passive"))
      (node (ref "U5") (pin "B5") (pinfunction "CC2_B5") (pintype "bidirectional"))
    )
    (net (code "94") (name "Net-(U8-I{slash}O1_OUT)") (class "Default")
      (node (ref "R6") (pin "1") (pinfunction "1_1") (pintype "passive"))
      (node (ref "U8") (pin "6") (pinfunction "I/O1_OUT_6") (pintype "bidirectional"))
    )
    (net (code "95") (name "Net-(U8-I{slash}O2_OUT)") (class "Default")
      (node (ref "R7") (pin "1") (pinfunction "1_1") (pintype "passive"))
      (node (ref "U8") (pin "4") (pinfunction "I/O2_OUT_4") (pintype "bidirectional"))
    )
    (net (code "96") (name "Net-(U9-V3)") (class "Default")
      (node (ref "C11") (pin "1") (pinfunction "1_1") (pintype "passive"))
      (node (ref "U9") (pin "4") (pinfunction "V3_4") (pintype "power_in"))
    )
    (net (code "97") (name "Net-(U10-DOUT)") (class "Default")
      (node (ref "U10") (pin "24") (pinfunction "DOUT_24") (pintype "output"))
      (node (ref "U11") (pin "1") (pinfunction "DIN_1") (pintype "input"))
    )
    (net (code "98") (name "Net-(U10-ISET)") (class "Default")
      (node (ref "R8") (pin "2") (pinfunction "2_2") (pintype "passive"))
      (node (ref "U10") (pin "18") (pinfunction "ISET_18") (pintype "bidirectional"))
    )
    (net (code "99") (name "Net-(U11-ISET)") (class "Default")
      (node (ref "R9") (pin "2") (pinfunction "2_2") (pintype "passive"))
      (node (ref "U11") (pin "18") (pinfunction "ISET_18") (pintype "bidirectional"))
    )
    (net (code "100") (name "Net-(U12-VCAP)") (class "Default")
      (node (ref "C17") (pin "1") (pinfunction "1_1") (pintype "passive"))
      (node (ref "U12") (pin "8") (pinfunction "VCAP_8") (pintype "passive"))
    )
    (net (code "101") (name "Net-(U13-IN+)") (class "Default")
      (node (ref "C20") (pin "1") (pinfunction "1_1") (pintype "passive"))
      (node (ref "R13") (pin "2") (pinfunction "2_2") (pintype "passive"))
      (node (ref "R14") (pin "1") (pinfunction "1_1") (pintype "passive"))
      (node (ref "U13") (pin "1") (pinfunction "IN+_1") (pintype "passive"))
    )
    (net (code "102") (name "Net-(U13-IN-)") (class "Default")
      (node (ref "C22") (pin "2") (pinfunction "2_2") (pintype "passive"))
      (node (ref "R15") (pin "1") (pinfunction "1_1") (pintype "passive"))
      (node (ref "R16") (pin "1") (pinfunction "1_1") (pintype "passive"))
      (node (ref "U13") (pin "3") (pinfunction "IN-_3") (pintype "passive"))
    )
    (net (code "103") (name "unconnected-(U5-SBU1-PadA8)") (class "Default")
      (node (ref "U5") (pin "A8") (pinfunction "SBU1_A8") (pintype "bidirectional+no_connect"))
    )
    (net (code "104") (name "unconnected-(U5-SBU2-PadB8)") (class "Default")
      (node (ref "U5") (pin "B8") (pinfunction "SBU2_B8") (pintype "bidirectional+no_connect"))
    )
    (net (code "105") (name "unconnected-(U9-NC.-Pad7)") (class "Default")
      (node (ref "U9") (pin "7") (pinfunction "NC._7") (pintype "passive+no_connect"))
    )
    (net (code "106") (name "unconnected-(U9-R232-Pad15)") (class "Default")
      (node (ref "U9") (pin "15") (pinfunction "R232_15") (pintype "input+no_connect"))
    )
    (net (code "107") (name "unconnected-(U9-~{CTS}-Pad9)") (class "Default")
      (node (ref "U9") (pin "9") (pinfunction "~{CTS}_9") (pintype "input+no_connect"))
    )
    (net (code "108") (name "unconnected-(U9-~{DCD}-Pad12)") (class "Default")
      (node (ref "U9") (pin "12") (pinfunction "~{DCD}_12") (pintype "input+no_connect"))
    )
    (net (code "109") (name "unconnected-(U9-~{DSR}-Pad10)") (class "Default")
      (node (ref "U9") (pin "10") (pinfunction "~{DSR}_10") (pintype "input+no_connect"))
    )
    (net (code "110") (name "unconnected-(U9-~{DTR}-Pad13)") (class "Default")
      (node (ref "U9") (pin "13") (pinfunction "~{DTR}_13") (pintype "output+no_connect"))
    )
    (net (code "111") (name "unconnected-(U9-~{OUT}-Pad8)") (class "Default")
      (node (ref "U9") (pin "8") (pinfunction "~{OUT}_8") (pintype "output+no_connect"))
    )
    (net (code "112") (name "unconnected-(U9-~{RI}-Pad11)") (class "Default")
      (node (ref "U9") (pin "11") (pinfunction "~{RI}_11") (pintype "input+no_connect"))
    )
    (net (code "113") (name "unconnected-(U9-~{RTS}-Pad14)") (class "Default")
      (node (ref "U9") (pin "14") (pinfunction "~{RTS}_14") (pintype "output+no_connect"))
    )
    (net (code "114") (name "unconnected-(U11-DOUT-Pad24)") (class "Default")
      (node (ref "U11") (pin "24") (pinfunction "DOUT_24") (pintype "output"))
    )
    (net (code "115") (name "unconnected-(U12-OSCIN_PA1-Pad5)") (class "Default")
      (node (ref "U12") (pin "5") (pinfunction "OSCIN_PA1_5") (pintype "bidirectional+no_connect"))
    )
    (net (code "116") (name "unconnected-(U12-OSCOUT{slash}PA2-Pad6)") (class "Default")
      (node (ref "U12") (pin "6") (pinfunction "OSCOUT/PA2_6") (pintype "bidirectional+no_connect"))
    )
    (net (code "117") (name "unconnected-(U12-PB4(T){slash}I2C_SCL[ADC_ETR]-Pad12)") (class "Default")
      (node (ref "U12") (pin "12") (pinfunction "PB4(T)/I2C_SCL[ADC_ETR]_12") (pintype "bidirectional+no_connect"))
    )
    (net (code "118") (name "unconnected-(U12-PB5(T){slash}I2C_SDA[TIM1_BKIN]-Pad11)") (class "Default")
      (node (ref "U12") (pin "11") (pinfunction "PB5(T)/I2C_SDA[TIM1_BKIN]_11") (pintype "bidirectional+no_connect"))
    )
    (net (code "119") (name "unconnected-(U12-PC3(HS){slash}TIM1_CH3[TLI][TIM1_CH1N]-Pad13)") (class "Default")
      (node (ref "U12") (pin "13") (pinfunction "PC3(HS)/TIM1_CH3[TLI][TIM1_CH1N]_13") (pintype "bidirectional+no_connect"))
    )
    (net (code "120") (name "unconnected-(U12-PC7(HS){slash}SPI_MISO[TIM1_CH2]-Pad17)") (class "Default")
      (node (ref "U12") (pin "17") (pinfunction "PC7(HS)/SPI_MISO[TIM1_CH2]_17") (pintype "bidirectional+no_connect"))
    )
    (net (code "121") (name "unconnected-(U12-PD2(HS){slash}AIN3{slash}[TIM2_CH3]-Pad19)") (class "Default")
      (node (ref "U12") (pin "19") (pinfunction "PD2(HS)/AIN3/[TIM2_CH3]_19") (pintype "bidirectional+no_connect"))
    )
    (net (code "122") (name "unconnected-(U12-PD3(HS){slash}AIN4{slash}TIM2_CH2{slash}ADC_ETR-Pad20)") (class "Default")
      (node (ref "U12") (pin "20") (pinfunction "PD3(HS)/AIN4/TIM2_CH2/ADC_ETR_20") (pintype "bidirectional+no_connect"))
    )
    (net (code "123") (name "unconnected-(U12-UART1_CK{slash}TIM2_CH1{slash}BEEP{slash}(HS)PD4-Pad1)") (class "Default")
      (node (ref "U12") (pin "1") (pinfunction "UART1_CK/TIM2_CH1/BEEP/(HS)PD4_1") (pintype "bidirectional+no_connect"))
    )
  )
)
